# RCShield-v2.net
KiCad netlist of a schematic drawn in EAGLE
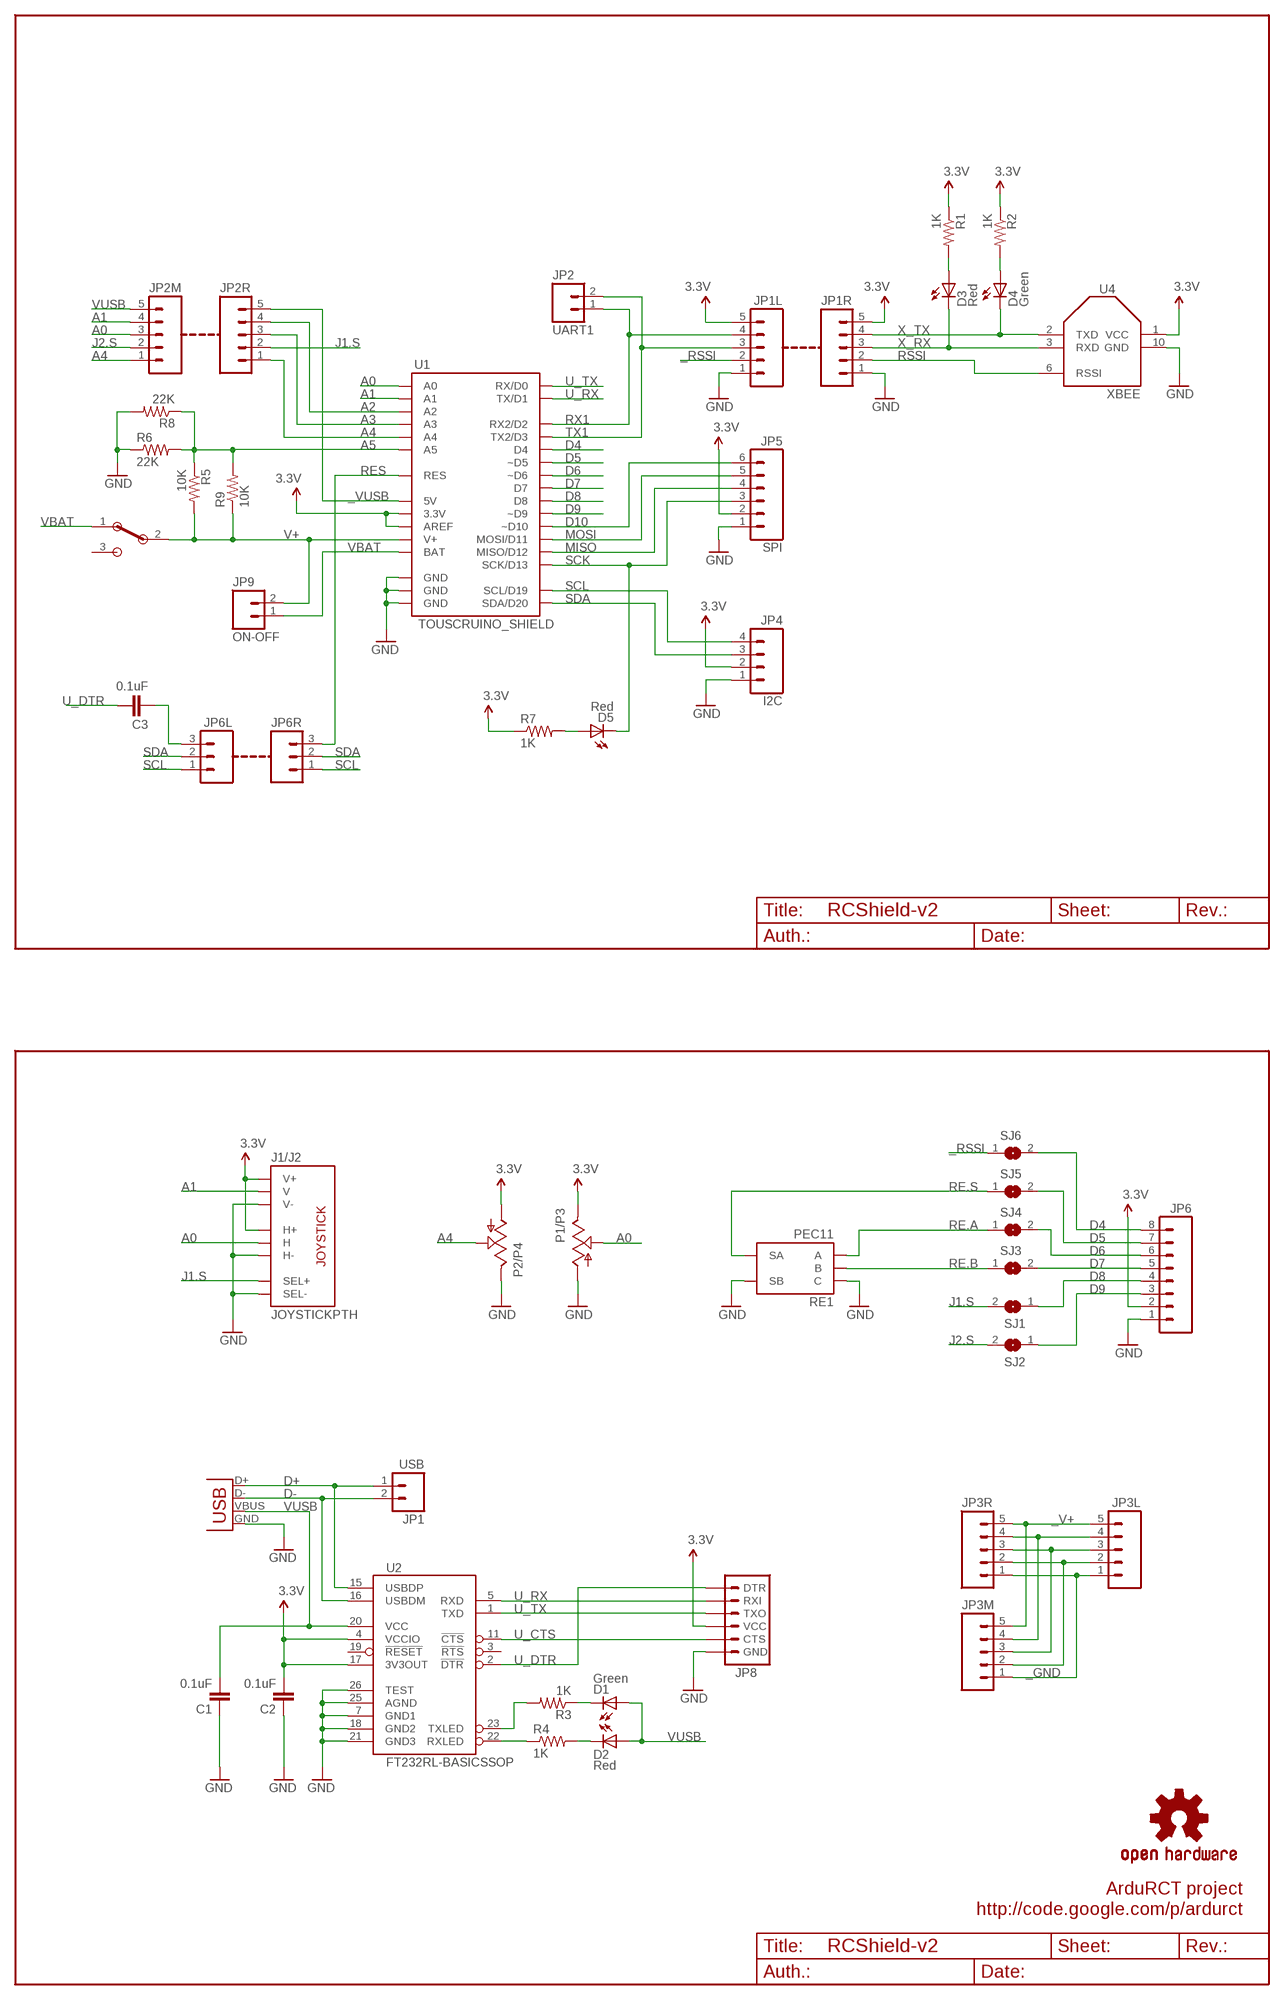
[diagram p0: schematic, sheet 1]

(export (version "E")
  (design (tool "Eeschema 10.0.6"))
  (components
    (comp (ref "C1")
      (value "0.1uF")
      (footprint "eagle-import:0805")
      (libsource (lib "eagle-import") (part "CAP0805"))
    )
    (comp (ref "C2")
      (value "0.1uF")
      (footprint "eagle-import:0805")
      (libsource (lib "eagle-import") (part "CAP0805"))
    )
    (comp (ref "C3")
      (value "0.1uF")
      (footprint "eagle-import:0805")
      (libsource (lib "eagle-import") (part "CAP0805"))
    )
    (comp (ref "D1")
      (value "Green")
      (footprint "eagle-import:LED")
      (libsource (lib "eagle-import") (part "LED"))
    )
    (comp (ref "D2")
      (value "Red")
      (footprint "eagle-import:LED")
      (libsource (lib "eagle-import") (part "LED"))
    )
    (comp (ref "D3")
      (value "Red")
      (footprint "eagle-import:LED")
      (libsource (lib "eagle-import") (part "LED"))
    )
    (comp (ref "D4")
      (value "Green")
      (footprint "eagle-import:LED")
      (libsource (lib "eagle-import") (part "LED"))
    )
    (comp (ref "D5")
      (value "Red")
      (footprint "eagle-import:LED")
      (libsource (lib "eagle-import") (part "LED"))
    )
    (comp (ref "J1/J2")
      (value "JOYSTICKPTH")
      (footprint "eagle-import:JOYSTICK")
      (libsource (lib "eagle-import") (part "JOYSTICKPTH"))
    )
    (comp (ref "JP1")
      (value "USB")
      (footprint "eagle-import:1X02")
      (libsource (lib "eagle-import") (part "M02"))
    )
    (comp (ref "JP1L")
      (value "M05")
      (footprint "eagle-import:2+3")
      (libsource (lib "eagle-import") (part "M05"))
    )
    (comp (ref "JP1R")
      (value "M05")
      (footprint "eagle-import:2+3")
      (libsource (lib "eagle-import") (part "M05"))
    )
    (comp (ref "JP2")
      (value "UART1")
      (footprint "eagle-import:1X02")
      (libsource (lib "eagle-import") (part "M02"))
    )
    (comp (ref "JP2M")
      (value "M05")
      (footprint "eagle-import:2+3")
      (libsource (lib "eagle-import") (part "M05"))
    )
    (comp (ref "JP2R")
      (value "M05")
      (footprint "eagle-import:2+3")
      (libsource (lib "eagle-import") (part "M05"))
    )
    (comp (ref "JP3L")
      (value "M05")
      (footprint "eagle-import:2+3")
      (libsource (lib "eagle-import") (part "M05"))
    )
    (comp (ref "JP3M")
      (value "M05")
      (footprint "eagle-import:2+3")
      (libsource (lib "eagle-import") (part "M05"))
    )
    (comp (ref "JP3R")
      (value "M05")
      (footprint "eagle-import:2+3")
      (libsource (lib "eagle-import") (part "M05"))
    )
    (comp (ref "JP4")
      (value "I2C")
      (footprint "eagle-import:1X04")
      (libsource (lib "eagle-import") (part "M04"))
    )
    (comp (ref "JP5")
      (value "SPI")
      (footprint "eagle-import:1X06")
      (libsource (lib "eagle-import") (part "M06SIP"))
    )
    (comp (ref "JP6")
      (value "M08")
      (footprint "eagle-import:1X08")
      (libsource (lib "eagle-import") (part "M08"))
    )
    (comp (ref "JP6L")
      (value "M03PTH")
      (footprint "eagle-import:1X03")
      (libsource (lib "eagle-import") (part "M03PTH"))
    )
    (comp (ref "JP6R")
      (value "M03PTH")
      (footprint "eagle-import:1X03")
      (libsource (lib "eagle-import") (part "M03PTH"))
    )
    (comp (ref "JP8")
      (value "ARDUINO_SERIAL_PROGRAM")
      (footprint "eagle-import:1X06_F")
      (libsource (lib "eagle-import") (part "ARDUINO_SERIAL_PROGRAM"))
    )
    (comp (ref "JP9")
      (value "ON-OFF")
      (footprint "eagle-import:1X02")
      (libsource (lib "eagle-import") (part "M02"))
    )
    (comp (ref "P1/P3")
      (value "POT")
      (footprint "eagle-import:ALPS_POT")
      (libsource (lib "eagle-import") (part "POT"))
    )
    (comp (ref "P2/P4")
      (value "POT")
      (footprint "eagle-import:ALPS_POT")
      (libsource (lib "eagle-import") (part "POT"))
    )
    (comp (ref "R1")
      (value "1K")
      (footprint "eagle-import:0805")
      (libsource (lib "eagle-import") (part "RESISTOR0805-RES"))
    )
    (comp (ref "R2")
      (value "1K")
      (footprint "eagle-import:0805")
      (libsource (lib "eagle-import") (part "RESISTOR0805-RES"))
    )
    (comp (ref "R3")
      (value "1K")
      (footprint "eagle-import:0805")
      (libsource (lib "eagle-import") (part "RESISTOR0805-RES"))
    )
    (comp (ref "R4")
      (value "1K")
      (footprint "eagle-import:0805")
      (libsource (lib "eagle-import") (part "RESISTOR0805-RES"))
    )
    (comp (ref "R5")
      (value "10K")
      (footprint "eagle-import:0805")
      (libsource (lib "eagle-import") (part "RESISTOR0805-RES"))
    )
    (comp (ref "R6")
      (value "22K")
      (footprint "eagle-import:0805")
      (libsource (lib "eagle-import") (part "RESISTOR0805-RES"))
    )
    (comp (ref "R7")
      (value "1K")
      (footprint "eagle-import:0805")
      (libsource (lib "eagle-import") (part "RESISTOR0805-RES"))
    )
    (comp (ref "R8")
      (value "22K")
      (footprint "eagle-import:0207_7")
      (libsource (lib "eagle-import") (part "R-US_0207/7"))
    )
    (comp (ref "R9")
      (value "10K")
      (footprint "eagle-import:0207_7")
      (libsource (lib "eagle-import") (part "R-US_0207/7"))
    )
    (comp (ref "RE1")
      (value "PEC11")
      (footprint "eagle-import:PEC11")
      (libsource (lib "eagle-import") (part "PEC11"))
    )
    (comp (ref "S4")
      (value "EG1224")
      (footprint "eagle-import:EG1224")
      (libsource (lib "eagle-import") (part "EG1224"))
    )
    (comp (ref "SJ1") (value "SJ") (footprint "eagle-import:SJ") (libsource (lib "eagle-import") (part "SJ")))
    (comp (ref "SJ2") (value "SJ") (footprint "eagle-import:SJ") (libsource (lib "eagle-import") (part "SJ")))
    (comp (ref "SJ3") (value "SJ") (footprint "eagle-import:SJ") (libsource (lib "eagle-import") (part "SJ")))
    (comp (ref "SJ4") (value "SJ") (footprint "eagle-import:SJ") (libsource (lib "eagle-import") (part "SJ")))
    (comp (ref "SJ5") (value "SJ") (footprint "eagle-import:SJ") (libsource (lib "eagle-import") (part "SJ")))
    (comp (ref "SJ6") (value "SJ") (footprint "eagle-import:SJ") (libsource (lib "eagle-import") (part "SJ")))
    (comp (ref "U$1")
      (value "OSHW-LOGOM")
      (footprint "eagle-import:OSHW-LOGO-M")
      (libsource (lib "eagle-import") (part "OSHW-LOGOM"))
    )
    (comp (ref "U1")
      (value "TOUSCRUINO_SHIELD")
      (footprint "eagle-import:TOUSCRUINO_SHIELD_SPLIT")
      (libsource (lib "eagle-import") (part "TOUSCRUINO_SHIELDSPLIT"))
    )
    (comp (ref "U2")
      (value "FT232RL-BASICSSOP")
      (footprint "eagle-import:SSOP28DB")
      (libsource (lib "eagle-import") (part "FT232RL-BASICSSOP"))
    )
    (comp (ref "U4")
      (value "XBEE")
      (footprint "eagle-import:XBEE-SMD")
      (libsource (lib "eagle-import") (part "XBEE-RSSI"))
    )
    (comp (ref "X1")
      (value "USBSMD")
      (footprint "eagle-import:USB-MINIB")
      (libsource (lib "eagle-import") (part "USBSMD"))
    )
  )
  (nets
    (net (code "1") (name "/A0") (class "Default")
      (node (ref "J1/J2") (pin "H2") (pinfunction "H_H2") (pintype "bidirectional"))
      (node (ref "JP2M") (pin "3") (pinfunction "3_3") (pintype "passive"))
      (node (ref "P1/P3") (pin "P$2") (pinfunction "S_P$2") (pintype "passive"))
      (node (ref "U1") (pin "A0") (pinfunction "A0_A0") (pintype "bidirectional"))
    )
    (net (code "2") (name "/A1") (class "Default")
      (node (ref "J1/J2") (pin "V2") (pinfunction "V_V2") (pintype "bidirectional"))
      (node (ref "JP2M") (pin "4") (pinfunction "4_4") (pintype "passive"))
      (node (ref "U1") (pin "A1") (pinfunction "A1_A1") (pintype "bidirectional"))
    )
    (net (code "3") (name "/A2") (class "Default")
      (node (ref "JP2R") (pin "4") (pinfunction "4_4") (pintype "passive"))
      (node (ref "U1") (pin "A2") (pinfunction "A2_A2") (pintype "bidirectional"))
    )
    (net (code "4") (name "/A3") (class "Default")
      (node (ref "JP2R") (pin "3") (pinfunction "3_3") (pintype "passive"))
      (node (ref "U1") (pin "A3") (pinfunction "A3_A3") (pintype "bidirectional"))
    )
    (net (code "5") (name "/A4") (class "Default")
      (node (ref "JP2M") (pin "1") (pinfunction "1_1") (pintype "passive"))
      (node (ref "JP2R") (pin "1") (pinfunction "1_1") (pintype "passive"))
      (node (ref "P2/P4") (pin "P$2") (pinfunction "S_P$2") (pintype "passive"))
      (node (ref "U1") (pin "A4") (pinfunction "A4_A4") (pintype "bidirectional"))
    )
    (net (code "6") (name "/A5") (class "Default")
      (node (ref "R5") (pin "1") (pinfunction "1_1") (pintype "passive"))
      (node (ref "R6") (pin "2") (pinfunction "2_2") (pintype "passive"))
      (node (ref "R8") (pin "1") (pinfunction "1_1") (pintype "passive"))
      (node (ref "R9") (pin "2") (pinfunction "2_2") (pintype "passive"))
      (node (ref "U1") (pin "A5") (pinfunction "A5_A5") (pintype "bidirectional"))
    )
    (net (code "7") (name "/D+") (class "Default")
      (node (ref "JP1") (pin "1") (pinfunction "1_1") (pintype "passive"))
      (node (ref "U2") (pin "15") (pinfunction "USBDP_15") (pintype "bidirectional"))
      (node (ref "X1") (pin "D+") (pinfunction "D+_D+") (pintype "bidirectional"))
    )
    (net (code "8") (name "/D-") (class "Default")
      (node (ref "JP1") (pin "2") (pinfunction "2_2") (pintype "passive"))
      (node (ref "U2") (pin "16") (pinfunction "USBDM_16") (pintype "bidirectional"))
      (node (ref "X1") (pin "D-") (pinfunction "D-_D-") (pintype "bidirectional"))
    )
    (net (code "9") (name "/D4") (class "Default")
      (node (ref "JP6") (pin "8") (pinfunction "8_8") (pintype "passive"))
      (node (ref "SJ6") (pin "2") (pinfunction "2_2") (pintype "passive"))
      (node (ref "U1") (pin "D4") (pinfunction "D4_D4") (pintype "bidirectional"))
    )
    (net (code "10") (name "/D5") (class "Default")
      (node (ref "JP6") (pin "7") (pinfunction "7_7") (pintype "passive"))
      (node (ref "SJ5") (pin "2") (pinfunction "2_2") (pintype "passive"))
      (node (ref "U1") (pin "D5") (pinfunction "~{D5}_D5") (pintype "bidirectional"))
    )
    (net (code "11") (name "/D6") (class "Default")
      (node (ref "JP6") (pin "6") (pinfunction "6_6") (pintype "passive"))
      (node (ref "SJ4") (pin "2") (pinfunction "2_2") (pintype "passive"))
      (node (ref "U1") (pin "D6") (pinfunction "~{D6}_D6") (pintype "bidirectional"))
    )
    (net (code "12") (name "/D7") (class "Default")
      (node (ref "JP6") (pin "5") (pinfunction "5_5") (pintype "passive"))
      (node (ref "SJ3") (pin "2") (pinfunction "2_2") (pintype "passive"))
      (node (ref "U1") (pin "D7") (pinfunction "D7_D7") (pintype "bidirectional"))
    )
    (net (code "13") (name "/D8") (class "Default")
      (node (ref "JP6") (pin "4") (pinfunction "4_4") (pintype "passive"))
      (node (ref "SJ1") (pin "1") (pinfunction "1_1") (pintype "passive"))
      (node (ref "U1") (pin "D8") (pinfunction "D8_D8") (pintype "bidirectional"))
    )
    (net (code "14") (name "/D9") (class "Default")
      (node (ref "JP6") (pin "3") (pinfunction "3_3") (pintype "passive"))
      (node (ref "SJ2") (pin "1") (pinfunction "1_1") (pintype "passive"))
      (node (ref "U1") (pin "D9") (pinfunction "~{D9}_D9") (pintype "bidirectional"))
    )
    (net (code "15") (name "/D10") (class "Default")
      (node (ref "JP5") (pin "6") (pinfunction "6_6") (pintype "passive"))
      (node (ref "U1") (pin "D10") (pinfunction "~{D10}_D10") (pintype "bidirectional"))
    )
    (net (code "16") (name "/J1.S") (class "Default")
      (node (ref "J1/J2") (pin "B1A") (pinfunction "SEL+_B1A") (pintype "bidirectional"))
      (node (ref "JP2R") (pin "2") (pinfunction "2_2") (pintype "passive"))
      (node (ref "SJ1") (pin "2") (pinfunction "2_2") (pintype "passive"))
    )
    (net (code "17") (name "/J2.S") (class "Default")
      (node (ref "JP2M") (pin "2") (pinfunction "2_2") (pintype "passive"))
      (node (ref "SJ2") (pin "2") (pinfunction "2_2") (pintype "passive"))
    )
    (net (code "18") (name "/MISO") (class "Default")
      (node (ref "JP5") (pin "4") (pinfunction "4_4") (pintype "passive"))
      (node (ref "U1") (pin "D12") (pinfunction "MISO/D12_D12") (pintype "bidirectional"))
    )
    (net (code "19") (name "/MOSI") (class "Default")
      (node (ref "JP5") (pin "5") (pinfunction "5_5") (pintype "passive"))
      (node (ref "U1") (pin "D11") (pinfunction "MOSI/D11_D11") (pintype "bidirectional"))
    )
    (net (code "20") (name "/RE.A") (class "Default")
      (node (ref "RE1") (pin "A") (pinfunction "A_A") (pintype "bidirectional"))
      (node (ref "SJ4") (pin "1") (pinfunction "1_1") (pintype "passive"))
    )
    (net (code "21") (name "/RE.B") (class "Default")
      (node (ref "RE1") (pin "B") (pinfunction "B_B") (pintype "bidirectional"))
      (node (ref "SJ3") (pin "1") (pinfunction "1_1") (pintype "passive"))
    )
    (net (code "22") (name "/RE.S") (class "Default")
      (node (ref "RE1") (pin "S1") (pinfunction "SA_S1") (pintype "bidirectional"))
      (node (ref "SJ5") (pin "1") (pinfunction "1_1") (pintype "passive"))
    )
    (net (code "23") (name "/RES") (class "Default")
      (node (ref "JP6R") (pin "3") (pinfunction "3_3") (pintype "passive"))
      (node (ref "U1") (pin "RES") (pinfunction "RES_RES") (pintype "bidirectional"))
    )
    (net (code "24") (name "/RSSI") (class "Default")
      (node (ref "JP1R") (pin "2") (pinfunction "2_2") (pintype "passive"))
      (node (ref "U4") (pin "6") (pinfunction "RSSI_6") (pintype "bidirectional"))
    )
    (net (code "25") (name "/RX1") (class "Default")
      (node (ref "JP1L") (pin "4") (pinfunction "4_4") (pintype "passive"))
      (node (ref "JP2") (pin "1") (pinfunction "1_1") (pintype "passive"))
      (node (ref "U1") (pin "D2") (pinfunction "RX2/D2_D2") (pintype "bidirectional"))
    )
    (net (code "26") (name "/SCK") (class "Default")
      (node (ref "D5") (pin "C1") (pinfunction "C_C1") (pintype "passive"))
      (node (ref "JP5") (pin "3") (pinfunction "3_3") (pintype "passive"))
      (node (ref "U1") (pin "D13") (pinfunction "SCK/D13_D13") (pintype "bidirectional"))
    )
    (net (code "27") (name "/SCL") (class "Default")
      (node (ref "JP4") (pin "4") (pinfunction "4_4") (pintype "passive"))
      (node (ref "JP6L") (pin "1") (pinfunction "1_1") (pintype "passive"))
      (node (ref "JP6R") (pin "1") (pinfunction "1_1") (pintype "passive"))
      (node (ref "U1") (pin "SCL") (pinfunction "SCL/D19_SCL") (pintype "bidirectional"))
    )
    (net (code "28") (name "/SDA") (class "Default")
      (node (ref "JP4") (pin "3") (pinfunction "3_3") (pintype "passive"))
      (node (ref "JP6L") (pin "2") (pinfunction "2_2") (pintype "passive"))
      (node (ref "JP6R") (pin "2") (pinfunction "2_2") (pintype "passive"))
      (node (ref "U1") (pin "SDA") (pinfunction "SDA/D20_SDA") (pintype "bidirectional"))
    )
    (net (code "29") (name "/TX1") (class "Default")
      (node (ref "JP1L") (pin "3") (pinfunction "3_3") (pintype "passive"))
      (node (ref "JP2") (pin "2") (pinfunction "2_2") (pintype "passive"))
      (node (ref "U1") (pin "D3") (pinfunction "TX2/D3_D3") (pintype "bidirectional"))
    )
    (net (code "30") (name "/U_CTS") (class "Default")
      (node (ref "JP8") (pin "5") (pinfunction "CTS_5") (pintype "passive"))
      (node (ref "U2") (pin "11") (pinfunction "~{CTS}_11") (pintype "bidirectional"))
    )
    (net (code "31") (name "/U_DTR") (class "Default")
      (node (ref "C3") (pin "1") (pinfunction "1_1") (pintype "passive"))
      (node (ref "JP8") (pin "1") (pinfunction "DTR_1") (pintype "passive"))
      (node (ref "U2") (pin "2") (pinfunction "~{DTR}_2") (pintype "bidirectional"))
    )
    (net (code "32") (name "/U_RX") (class "Default")
      (node (ref "JP8") (pin "2") (pinfunction "RXI_2") (pintype "passive"))
      (node (ref "U1") (pin "TX") (pinfunction "TX/D1_TX") (pintype "bidirectional"))
      (node (ref "U2") (pin "5") (pinfunction "RXD_5") (pintype "input"))
    )
    (net (code "33") (name "/U_TX") (class "Default")
      (node (ref "JP8") (pin "3") (pinfunction "TXO_3") (pintype "passive"))
      (node (ref "U1") (pin "RX") (pinfunction "RX/D0_RX") (pintype "bidirectional"))
      (node (ref "U2") (pin "1") (pinfunction "TXD_1") (pintype "output"))
    )
    (net (code "34") (name "/V+") (class "Default")
      (node (ref "JP9") (pin "2") (pinfunction "2_2") (pintype "passive"))
      (node (ref "R5") (pin "2") (pinfunction "2_2") (pintype "passive"))
      (node (ref "R9") (pin "1") (pinfunction "1_1") (pintype "passive"))
      (node (ref "S4") (pin "2") (pinfunction "2_2") (pintype "bidirectional"))
      (node (ref "U1") (pin "V+") (pinfunction "V+_V+") (pintype "bidirectional"))
    )
    (net (code "35") (name "/VBAT") (class "Default")
      (node (ref "JP9") (pin "1") (pinfunction "1_1") (pintype "passive"))
      (node (ref "S4") (pin "1") (pinfunction "1_1") (pintype "bidirectional"))
      (node (ref "U1") (pin "BAT") (pinfunction "BAT_BAT") (pintype "bidirectional"))
    )
    (net (code "36") (name "/VUSB") (class "Default")
      (node (ref "C1") (pin "2") (pinfunction "2_2") (pintype "passive"))
      (node (ref "D1") (pin "A1") (pinfunction "A_A1") (pintype "passive"))
      (node (ref "D2") (pin "A1") (pinfunction "A_A1") (pintype "passive"))
      (node (ref "JP2M") (pin "5") (pinfunction "5_5") (pintype "passive"))
      (node (ref "U2") (pin "20") (pinfunction "VCC_20") (pintype "bidirectional"))
      (node (ref "X1") (pin "VBUS") (pinfunction "VBUS_VBUS") (pintype "bidirectional"))
    )
    (net (code "37") (name "/X_RX") (class "Default")
      (node (ref "D3") (pin "C1") (pinfunction "C_C1") (pintype "passive"))
      (node (ref "JP1R") (pin "3") (pinfunction "3_3") (pintype "passive"))
      (node (ref "U4") (pin "3") (pinfunction "RXD_3") (pintype "bidirectional"))
    )
    (net (code "38") (name "/X_TX") (class "Default")
      (node (ref "D4") (pin "C1") (pinfunction "C_C1") (pintype "passive"))
      (node (ref "JP1R") (pin "4") (pinfunction "4_4") (pintype "passive"))
      (node (ref "U4") (pin "2") (pinfunction "TXD_2") (pintype "bidirectional"))
    )
    (net (code "39") (name "/_GND") (class "Default")
      (node (ref "JP3L") (pin "1") (pinfunction "1_1") (pintype "passive"))
      (node (ref "JP3M") (pin "1") (pinfunction "1_1") (pintype "passive"))
      (node (ref "JP3R") (pin "1") (pinfunction "1_1") (pintype "passive"))
    )
    (net (code "40") (name "/_RSSI") (class "Default")
      (node (ref "JP1L") (pin "2") (pinfunction "2_2") (pintype "passive"))
      (node (ref "SJ6") (pin "1") (pinfunction "1_1") (pintype "passive"))
    )
    (net (code "41") (name "/_V+") (class "Default")
      (node (ref "JP3L") (pin "5") (pinfunction "5_5") (pintype "passive"))
      (node (ref "JP3M") (pin "5") (pinfunction "5_5") (pintype "passive"))
      (node (ref "JP3R") (pin "5") (pinfunction "5_5") (pintype "passive"))
    )
    (net (code "42") (name "/_VUSB") (class "Default")
      (node (ref "JP2R") (pin "5") (pinfunction "5_5") (pintype "passive"))
      (node (ref "U1") (pin "5V") (pinfunction "5V_5V") (pintype "bidirectional"))
    )
    (net (code "43") (name "3.3V") (class "Default")
      (node (ref "C2") (pin "2") (pinfunction "2_2") (pintype "passive"))
      (node (ref "J1/J2") (pin "H1") (pinfunction "H+_H1") (pintype "bidirectional"))
      (node (ref "J1/J2") (pin "V1") (pinfunction "V+_V1") (pintype "bidirectional"))
      (node (ref "JP1L") (pin "5") (pinfunction "5_5") (pintype "passive"))
      (node (ref "JP1R") (pin "5") (pinfunction "5_5") (pintype "passive"))
      (node (ref "JP4") (pin "2") (pinfunction "2_2") (pintype "passive"))
      (node (ref "JP5") (pin "2") (pinfunction "2_2") (pintype "passive"))
      (node (ref "JP6") (pin "2") (pinfunction "2_2") (pintype "passive"))
      (node (ref "JP8") (pin "4") (pinfunction "VCC_4") (pintype "passive"))
      (node (ref "P1/P3") (pin "P$1") (pinfunction "E_P$1") (pintype "passive"))
      (node (ref "P2/P4") (pin "P$3") (pinfunction "A_P$3") (pintype "passive"))
      (node (ref "R1") (pin "1") (pinfunction "1_1") (pintype "passive"))
      (node (ref "R2") (pin "1") (pinfunction "1_1") (pintype "passive"))
      (node (ref "R7") (pin "1") (pinfunction "1_1") (pintype "passive"))
      (node (ref "U1") (pin "3.3V") (pinfunction "3.3V_3.3V") (pintype "bidirectional"))
      (node (ref "U1") (pin "AREF") (pinfunction "AREF_AREF") (pintype "bidirectional"))
      (node (ref "U2") (pin "17") (pinfunction "3V3OUT_17") (pintype "output"))
      (node (ref "U2") (pin "4") (pinfunction "VCCIO_4") (pintype "bidirectional"))
      (node (ref "U4") (pin "1") (pinfunction "VCC_1") (pintype "bidirectional"))
    )
    (net (code "44") (name "GND") (class "Default")
      (node (ref "C1") (pin "1") (pinfunction "1_1") (pintype "passive"))
      (node (ref "C2") (pin "1") (pinfunction "1_1") (pintype "passive"))
      (node (ref "J1/J2") (pin "B2A") (pinfunction "SEL-_B2A") (pintype "bidirectional"))
      (node (ref "J1/J2") (pin "H3") (pinfunction "H-_H3") (pintype "bidirectional"))
      (node (ref "J1/J2") (pin "V3") (pinfunction "V-_V3") (pintype "bidirectional"))
      (node (ref "JP1L") (pin "1") (pinfunction "1_1") (pintype "passive"))
      (node (ref "JP1R") (pin "1") (pinfunction "1_1") (pintype "passive"))
      (node (ref "JP4") (pin "1") (pinfunction "1_1") (pintype "passive"))
      (node (ref "JP5") (pin "1") (pinfunction "1_1") (pintype "passive"))
      (node (ref "JP6") (pin "1") (pinfunction "1_1") (pintype "passive"))
      (node (ref "JP8") (pin "6") (pinfunction "GND_6") (pintype "passive"))
      (node (ref "P1/P3") (pin "P$3") (pinfunction "A_P$3") (pintype "passive"))
      (node (ref "P2/P4") (pin "P$1") (pinfunction "E_P$1") (pintype "passive"))
      (node (ref "R6") (pin "1") (pinfunction "1_1") (pintype "passive"))
      (node (ref "R8") (pin "2") (pinfunction "2_2") (pintype "passive"))
      (node (ref "RE1") (pin "C") (pinfunction "C_C") (pintype "bidirectional"))
      (node (ref "RE1") (pin "S2") (pinfunction "SB_S2") (pintype "bidirectional"))
      (node (ref "U1") (pin "GND@0") (pinfunction "GND_GND@0") (pintype "bidirectional"))
      (node (ref "U1") (pin "GND@1") (pinfunction "GND_GND@1") (pintype "bidirectional"))
      (node (ref "U1") (pin "GND@2") (pinfunction "GND_GND@2") (pintype "bidirectional"))
      (node (ref "U2") (pin "18") (pinfunction "GND2_18") (pintype "bidirectional"))
      (node (ref "U2") (pin "21") (pinfunction "GND3_21") (pintype "bidirectional"))
      (node (ref "U2") (pin "25") (pinfunction "AGND_25") (pintype "bidirectional"))
      (node (ref "U2") (pin "26") (pinfunction "TEST_26") (pintype "input"))
      (node (ref "U2") (pin "7") (pinfunction "GND1_7") (pintype "bidirectional"))
      (node (ref "U4") (pin "10") (pinfunction "GND_10") (pintype "bidirectional"))
      (node (ref "X1") (pin "GND") (pinfunction "GND_GND") (pintype "bidirectional"))
    )
    (net (code "45") (name "Net-(C3-Pad2)") (class "Default")
      (node (ref "C3") (pin "2") (pinfunction "2_2") (pintype "passive"))
      (node (ref "JP6L") (pin "3") (pinfunction "3_3") (pintype "passive"))
    )
    (net (code "46") (name "Net-(D1-C)") (class "Default")
      (node (ref "D1") (pin "C1") (pinfunction "C_C1") (pintype "passive"))
      (node (ref "R3") (pin "1") (pinfunction "1_1") (pintype "passive"))
    )
    (net (code "47") (name "Net-(D2-C)") (class "Default")
      (node (ref "D2") (pin "C1") (pinfunction "C_C1") (pintype "passive"))
      (node (ref "R4") (pin "2") (pinfunction "2_2") (pintype "passive"))
    )
    (net (code "48") (name "Net-(D3-A)") (class "Default")
      (node (ref "D3") (pin "A1") (pinfunction "A_A1") (pintype "passive"))
      (node (ref "R1") (pin "2") (pinfunction "2_2") (pintype "passive"))
    )
    (net (code "49") (name "Net-(D4-A)") (class "Default")
      (node (ref "D4") (pin "A1") (pinfunction "A_A1") (pintype "passive"))
      (node (ref "R2") (pin "2") (pinfunction "2_2") (pintype "passive"))
    )
    (net (code "50") (name "Net-(D5-A)") (class "Default")
      (node (ref "D5") (pin "A1") (pinfunction "A_A1") (pintype "passive"))
      (node (ref "R7") (pin "2") (pinfunction "2_2") (pintype "passive"))
    )
    (net (code "51") (name "Net-(JP3L-Pad2)") (class "Default")
      (node (ref "JP3L") (pin "2") (pinfunction "2_2") (pintype "passive"))
      (node (ref "JP3M") (pin "2") (pinfunction "2_2") (pintype "passive"))
      (node (ref "JP3R") (pin "2") (pinfunction "2_2") (pintype "passive"))
    )
    (net (code "52") (name "Net-(JP3L-Pad3)") (class "Default")
      (node (ref "JP3L") (pin "3") (pinfunction "3_3") (pintype "passive"))
      (node (ref "JP3M") (pin "3") (pinfunction "3_3") (pintype "passive"))
      (node (ref "JP3R") (pin "3") (pinfunction "3_3") (pintype "passive"))
    )
    (net (code "53") (name "Net-(JP3L-Pad4)") (class "Default")
      (node (ref "JP3L") (pin "4") (pinfunction "4_4") (pintype "passive"))
      (node (ref "JP3M") (pin "4") (pinfunction "4_4") (pintype "passive"))
      (node (ref "JP3R") (pin "4") (pinfunction "4_4") (pintype "passive"))
    )
    (net (code "54") (name "Net-(U2-RXLED)") (class "Default")
      (node (ref "R4") (pin "1") (pinfunction "1_1") (pintype "passive"))
      (node (ref "U2") (pin "22") (pinfunction "RXLED_22") (pintype "bidirectional"))
    )
    (net (code "55") (name "Net-(U2-TXLED)") (class "Default")
      (node (ref "R3") (pin "2") (pinfunction "2_2") (pintype "passive"))
      (node (ref "U2") (pin "23") (pinfunction "TXLED_23") (pintype "bidirectional"))
    )
    (net (code "56") (name "unconnected-(S4-Pad3)") (class "Default")
      (node (ref "S4") (pin "3") (pinfunction "3_3") (pintype "bidirectional"))
    )
    (net (code "57") (name "unconnected-(U2-~{RESET}-Pad19)") (class "Default")
      (node (ref "U2") (pin "19") (pinfunction "~{RESET}_19") (pintype "bidirectional"))
    )
    (net (code "58") (name "unconnected-(U2-~{RTS}-Pad3)") (class "Default")
      (node (ref "U2") (pin "3") (pinfunction "~{RTS}_3") (pintype "bidirectional"))
    )
  )
)
